# Daylight_Sensor_Network.net
KiCad netlist of a schematic drawn in Altium Designer
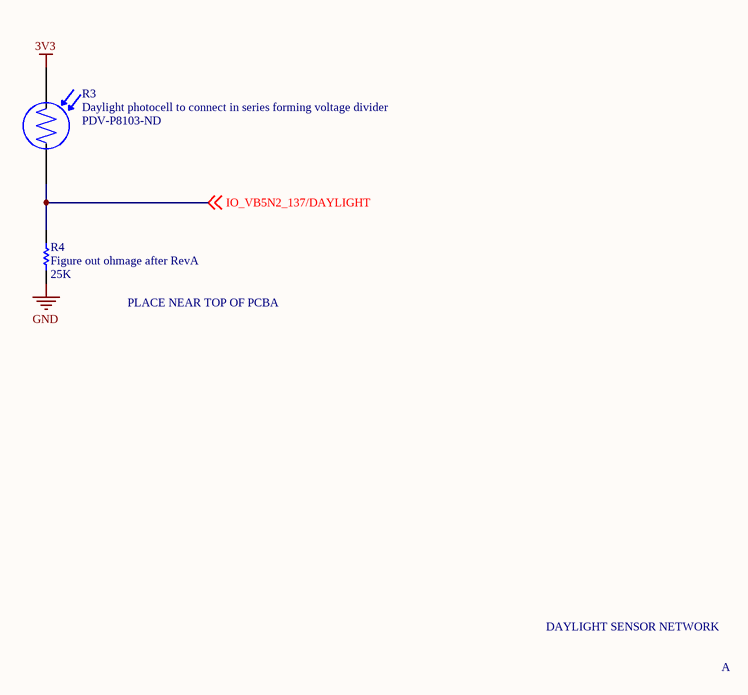
[diagram p0: Daylight_Sensor_Network.SchDoc]

(export (version "E")
  (design (tool "Eeschema 10.0.6"))
  (components
    (comp (ref "R3")
      (value "Daylight photocell to connect in series forming voltage divider")
      (footprint "RES_NSL-19M51")
      (description "http://media.digikey.com/pdf/Data%20Sheets/Photonic%20Detetectors%20Inc%20PDFs/PDV-P8103.pdf")
      (fields (field (name "SUPPLIER PART NUMBER 1") "PDV-P8103-ND"))
      (libsource (lib "schematics") (part "PHOTOCELL 16-33KOHM"))
    )
    (comp (ref "R4")
      (value "Figure out ohmage after RevA")
      (footprint "RES_0603")
      (description "Resistor")
      (fields (field (name "ALTIUM_VALUE") "25K") (field (name "PUBLISHER") "Altium Limited"))
      (libsource (lib "Miscellaneous Devices") (part "Res1"))
    )
  )
  (nets
    (net (code "1") (name "3V3") (class "Default")
      (node (ref "R3") (pin "1") (pinfunction "1_1") (pintype "passive"))
    )
    (net (code "2") (name "GND") (class "Default")
      (node (ref "R4") (pin "1") (pinfunction "1_1") (pintype "passive"))
    )
    (net (code "3") (name "IO_VB5N2_137{slash}DAYLIGHT") (class "Default")
      (node (ref "R3") (pin "2") (pinfunction "2_2") (pintype "passive"))
      (node (ref "R4") (pin "2") (pinfunction "2_2") (pintype "passive"))
    )
  )
)
